# Power.net
KiCad netlist of a schematic drawn in Altium Designer
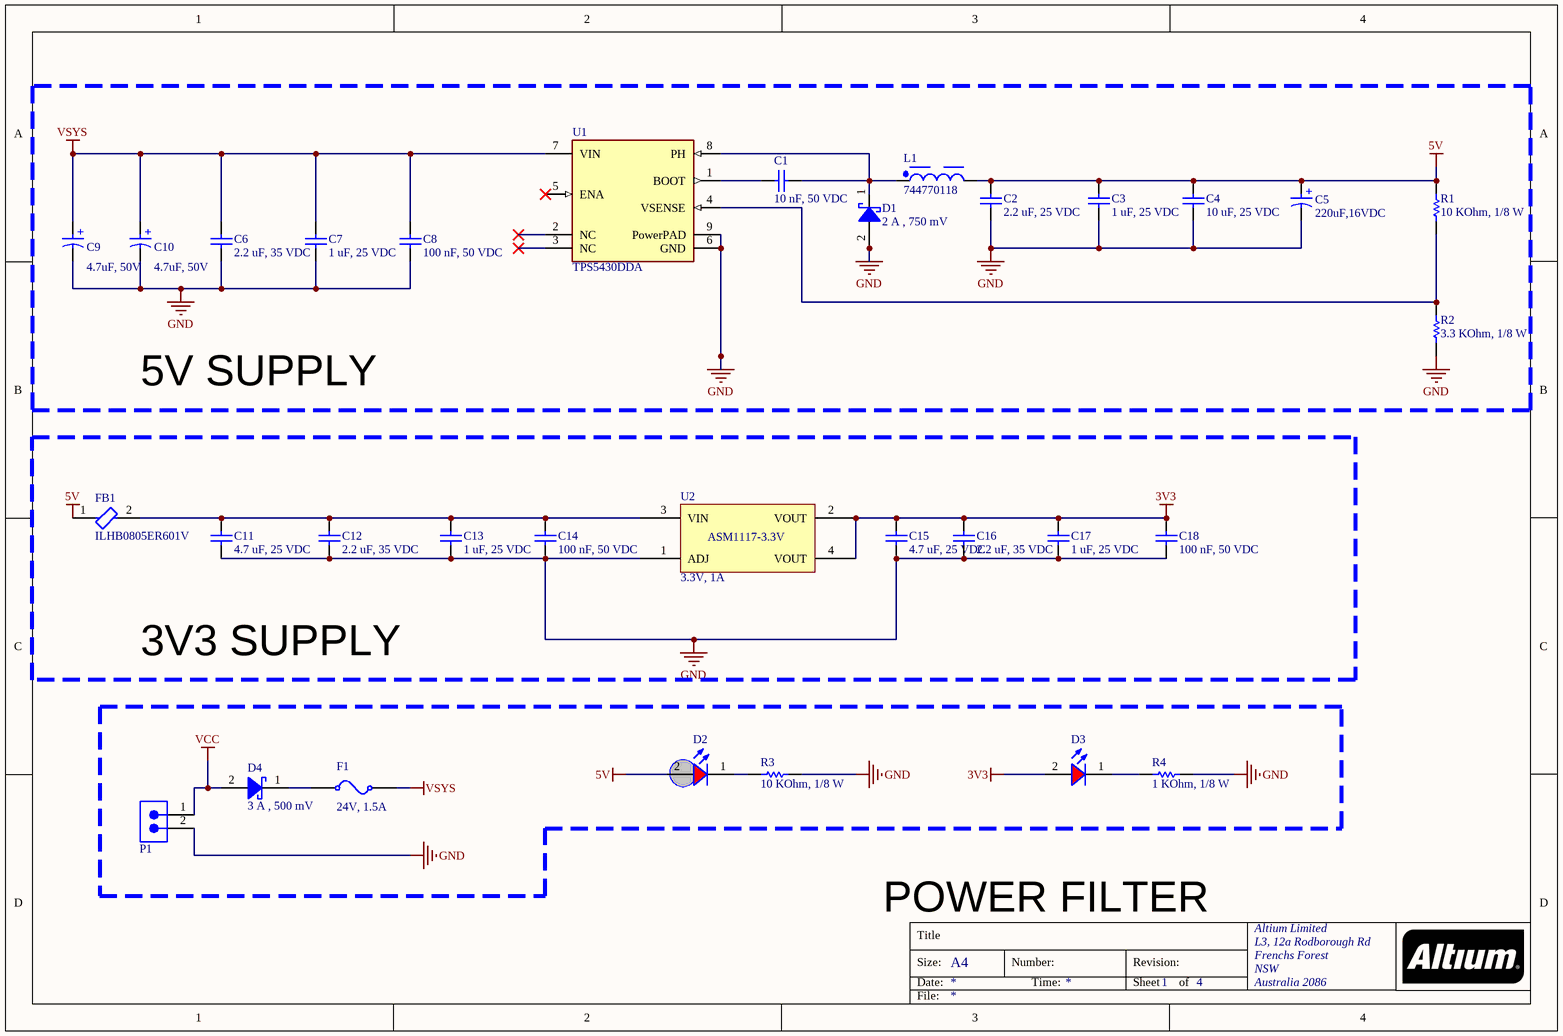
[diagram p0: Power.SchDoc]

(export (version "E")
  (design (tool "Eeschema 10.0.6"))
  (components
    (comp (ref "C1")
      (value "10 nF, 50 VDC")
      (footprint "CAP_0805")
      (description "CAP, size 0805, 10 nF, 50 VDC")
      (fields (field (name "TOLERANCE") "+/-5%"))
      (libsource (lib "Altium_Ceramic_Cap") (part "0108051031050"))
    )
    (comp (ref "C2")
      (value "2.2 uF, 25 VDC")
      (footprint "CAP_0805")
      (description "CAP, size 0805, 2.2 uF, 25 VDC")
      (fields (field (name "TOLERANCE") "+/-10%"))
      (libsource (lib "Altium_Ceramic_Cap") (part "0108052251025"))
    )
    (comp (ref "C3")
      (value "1 uF, 25 VDC")
      (footprint "CAP_0805")
      (description "CAP, size 0805, 1 uF, 25 VDC")
      (fields (field (name "TOLERANCE") "+/-10%"))
      (libsource (lib "Altium_Ceramic_Cap") (part "0108051051025"))
    )
    (comp (ref "C4")
      (value "10 uF, 25 VDC")
      (footprint "CAP_0805")
      (description "CAP, size 0805, 10 uF, 25 VDC")
      (fields (field (name "TOLERANCE") "+/-10%"))
      (libsource (lib "Altium_Ceramic_Cap") (part "0108051061025"))
    )
    (comp (ref "C5")
      (value "220uF,16VDC")
      (footprint "WCAP-ASLI_D6.3H7.7")
      (description "V-Chip, D6.3 x H7.7mm, 220uF, 16V")
      (fields (field (name "MANUFACTURER") "Wurth Elektronik"))
      (libsource (lib "Altium_Alutinum_Cap") (part "865080345012"))
    )
    (comp (ref "C6")
      (value "2.2 uF, 35 VDC")
      (footprint "CAP_0805")
      (description "CAP, size 0805, 2.2 uF, 35 VDC")
      (fields (field (name "TOLERANCE") "+/-10%"))
      (libsource (lib "Altium_Ceramic_Cap") (part "0108052251035"))
    )
    (comp (ref "C7")
      (value "1 uF, 25 VDC")
      (footprint "CAP_0805")
      (description "CAP, size 0805, 1 uF, 25 VDC")
      (fields (field (name "TOLERANCE") "+/-10%"))
      (libsource (lib "Altium_Ceramic_Cap") (part "0108051051025"))
    )
    (comp (ref "C8")
      (value "100 nF, 50 VDC")
      (footprint "CAP_0805")
      (description "CAP, size 0805, 100 nF, 50 VDC")
      (fields (field (name "TOLERANCE") "+/-10%"))
      (libsource (lib "Altium_Ceramic_Cap") (part "0108051041050"))
    )
    (comp (ref "C9")
      (value "4.7uF, 50V")
      (footprint "WCAP-ASLI_D4H5.5")
      (description "V-Chip, D4 x H5.5mm, 4.7uF, 50V")
      (fields (field (name "MANUFACTURER") "Wurth Elektronik"))
      (libsource (lib "Altium_Alutinum_Cap") (part "865080640004"))
    )
    (comp (ref "C10")
      (value "4.7uF, 50V")
      (footprint "WCAP-ASLI_D4H5.5")
      (description "V-Chip, D4 x H5.5mm, 4.7uF, 50V")
      (fields (field (name "MANUFACTURER") "Wurth Elektronik"))
      (libsource (lib "Altium_Alutinum_Cap") (part "865080640004"))
    )
    (comp (ref "C11")
      (value "4.7 uF, 25 VDC")
      (footprint "CAP_0805")
      (description "CAP, size 0805, 4.7 uF, 25 VDC")
      (fields (field (name "TOLERANCE") "+/-10%"))
      (libsource (lib "Altium_Ceramic_Cap") (part "0108054751025"))
    )
    (comp (ref "C12")
      (value "2.2 uF, 35 VDC")
      (footprint "CAP_0805")
      (description "CAP, size 0805, 2.2 uF, 35 VDC")
      (fields (field (name "TOLERANCE") "+/-10%"))
      (libsource (lib "Altium_Ceramic_Cap") (part "0108052251035"))
    )
    (comp (ref "C13")
      (value "1 uF, 25 VDC")
      (footprint "CAP_0805")
      (description "CAP, size 0805, 1 uF, 25 VDC")
      (fields (field (name "TOLERANCE") "+/-10%"))
      (libsource (lib "Altium_Ceramic_Cap") (part "0108051051025"))
    )
    (comp (ref "C14")
      (value "100 nF, 50 VDC")
      (footprint "CAP_0805")
      (description "CAP, size 0805, 100 nF, 50 VDC")
      (fields (field (name "TOLERANCE") "+/-10%"))
      (libsource (lib "Altium_Ceramic_Cap") (part "0108051041050"))
    )
    (comp (ref "C15")
      (value "4.7 uF, 25 VDC")
      (footprint "CAP_0805")
      (description "CAP, size 0805, 4.7 uF, 25 VDC")
      (fields (field (name "TOLERANCE") "+/-10%"))
      (libsource (lib "Altium_Ceramic_Cap") (part "0108054751025"))
    )
    (comp (ref "C16")
      (value "2.2 uF, 35 VDC")
      (footprint "CAP_0805")
      (description "CAP, size 0805, 2.2 uF, 35 VDC")
      (fields (field (name "TOLERANCE") "+/-10%"))
      (libsource (lib "Altium_Ceramic_Cap") (part "0108052251035"))
    )
    (comp (ref "C17")
      (value "1 uF, 25 VDC")
      (footprint "CAP_0805")
      (description "CAP, size 0805, 1 uF, 25 VDC")
      (fields (field (name "TOLERANCE") "+/-10%"))
      (libsource (lib "Altium_Ceramic_Cap") (part "0108051051025"))
    )
    (comp (ref "C18")
      (value "100 nF, 50 VDC")
      (footprint "CAP_0805")
      (description "CAP, size 0805, 100 nF, 50 VDC")
      (fields (field (name "TOLERANCE") "+/-10%"))
      (libsource (lib "Altium_Ceramic_Cap") (part "0108051041050"))
    )
    (comp (ref "D1")
      (value "2 A , 750 mV")
      (footprint "SMA (DO-214AC)")
      (description "Schottky Diodes & Rectifiers 2.0 Amp 60 Volt 40 Amp IFSM")
      (fields
        (field (name "MANUFACTURER") "Vishay Semiconductors")
        (field (name "MANUFACTURER PART NUMBER") "SS26S-E3/5AT")
      )
      (libsource (lib "Altium_Diode") (part "SS26"))
    )
    (comp (ref "D2")
      (value "Red, 2V")
      (footprint "WL-SMCW_0805")
      (description "WL-SMCW SMT Mono-color Chip LED Blur, size 0805, Red, 2V, 140deg")
      (libsource (lib "Altium_LED") (part "160805RedBlur"))
    )
    (comp (ref "D3")
      (value "Red, 2V")
      (footprint "WL-SMCW_0805")
      (description "WL-SMCW SMT Mono-color Chip LED Blur, size 0805, Red, 2V, 140deg")
      (libsource (lib "Altium_LED") (part "160805RedBlur"))
    )
    (comp (ref "D4")
      (value "3 A , 500 mV")
      (footprint "SMC (DO-214AB)")
      (description "Schottky Diodes & Rectifiers 3.0 Amp 40 Volt")
      (fields
        (field (name "MANUFACTURER") "Vishay Semiconductors")
        (field (name "MANUFACTURER PART NUMBER") "SS34-E3/57T")
      )
      (libsource (lib "Altium_Diode") (part "SS34"))
    )
    (comp (ref "F1")
      (value "24V, 1.5A")
      (footprint "Fuse_SMD_1812")
      (description "Resettable Fuse, Size 1812, 24V, 1.5A")
      (fields (field (name "MANUFACTURER") "Littelfuse"))
      (libsource (lib "Altium_Fuse") (part "061812150024"))
    )
    (comp (ref "FB1")
      (value "ILHB0805ER601V")
      (footprint "FP-ILHB-0805-IPC_C")
      (description "FERRITE BEAD 600 OHM 0805 1LN")
      (fields
        (field (name "TOLERANCE") "25%")
        (field (name "OCTOPART") "https://octopart.com/ilhb0805er601v-vishay-39650184")
      )
      (libsource (lib "Altium Content Vault") (part "5f30dd21d616792df468990f7003faa"))
    )
    (comp (ref "L1")
      (value "744770118")
      (footprint "WE-PD_1280")
      (libsource (lib "Altium Content Vault") (part "Inductor - 2"))
    )
    (comp (ref "P1")
      (value "20A, 300V")
      (footprint "Terminal-Block 2 pin")
      (fields
        (field (name "MANUFACTURER PART NUMBER") "691312510002")
        (field (name "MANUFACTURER") "Wurth Elektronik")
      )
      (libsource (lib "Altium_Terminal_Block") (part "691312510002"))
    )
    (comp (ref "R1")
      (value "10 KOhm, 1/8 W")
      (footprint "RESISTOR_0805")
      (description "RES, size 0805, 10 KOhm, 1/8 W")
      (libsource (lib "Altium_Resistor") (part "0008051035"))
    )
    (comp (ref "R2")
      (value "3.3 KOhm, 1/8 W")
      (footprint "RESISTOR_0805")
      (description "RES, size 0805, 3.3 KOhm, 1/8 W")
      (libsource (lib "Altium_Resistor") (part "0008053325"))
    )
    (comp (ref "R3")
      (value "10 KOhm, 1/8 W")
      (footprint "RESISTOR_0805")
      (description "RES, size 0805, 10 KOhm, 1/8 W")
      (libsource (lib "Altium_Resistor") (part "0008051031"))
    )
    (comp (ref "R4")
      (value "1 KOhm, 1/8 W")
      (footprint "RESISTOR_0805")
      (description "RES, size 0805, 1 KOhm, 1/8 W")
      (libsource (lib "Altium_Resistor") (part "0008051025"))
    )
    (comp (ref "U1")
      (value "TPS5430DDA")
      (footprint "FP-DDA0008J-MFG")
      (description "IC REG BUCK ADJUSTABLE 3A 8SOPWR")
      (fields
        (field (name "MANUFACTURER") "Texas Instruments")
        (field (name "OCTOPART") "https://octopart.com/tps5430dda-texas+instruments-589977")
      )
      (libsource (lib "Altium Content Vault") (part "98da629940cea6febc5630bb55159f3"))
    )
    (comp (ref "U2")
      (value "3.3V, 1A")
      (footprint "AMS1117-3.3V SOT223")
      (description "AMS1117-3.3V, OUT 3.3V 1A.")
      (fields (field (name "MANUFACTURER") "AMS"))
      (libsource (lib "Altium_Power_Supply_IC") (part "AMS1117-3.3V"))
    )
  )
  (nets
    (net (code "1") (name "3V3") (class "Default")
      (node (ref "C15") (pin "2") (pinfunction "2_2") (pintype "passive"))
      (node (ref "C16") (pin "2") (pinfunction "2_2") (pintype "passive"))
      (node (ref "C17") (pin "2") (pinfunction "2_2") (pintype "passive"))
      (node (ref "C18") (pin "2") (pinfunction "2_2") (pintype "passive"))
      (node (ref "D3") (pin "2") (pinfunction "A_2") (pintype "passive"))
      (node (ref "U2") (pin "2") (pinfunction "VOUT_2") (pintype "passive"))
      (node (ref "U2") (pin "4") (pinfunction "VOUT_4") (pintype "power_in"))
    )
    (net (code "2") (name "5V") (class "Default")
      (node (ref "C2") (pin "2") (pinfunction "2_2") (pintype "passive"))
      (node (ref "C3") (pin "2") (pinfunction "2_2") (pintype "passive"))
      (node (ref "C4") (pin "2") (pinfunction "2_2") (pintype "passive"))
      (node (ref "C5") (pin "1") (pinfunction "P_1") (pintype "passive"))
      (node (ref "D2") (pin "2") (pinfunction "A_2") (pintype "passive"))
      (node (ref "FB1") (pin "1") (pinfunction "1_1") (pintype "passive"))
      (node (ref "L1") (pin "2") (pinfunction "2_2") (pintype "passive"))
      (node (ref "R1") (pin "2") (pinfunction "2_2") (pintype "passive"))
    )
    (net (code "3") (name "GND") (class "Default")
      (node (ref "C10") (pin "2") (pinfunction "N_2") (pintype "passive"))
      (node (ref "C11") (pin "1") (pinfunction "1_1") (pintype "passive"))
      (node (ref "C12") (pin "1") (pinfunction "1_1") (pintype "passive"))
      (node (ref "C13") (pin "1") (pinfunction "1_1") (pintype "passive"))
      (node (ref "C14") (pin "1") (pinfunction "1_1") (pintype "passive"))
      (node (ref "C15") (pin "1") (pinfunction "1_1") (pintype "passive"))
      (node (ref "C16") (pin "1") (pinfunction "1_1") (pintype "passive"))
      (node (ref "C17") (pin "1") (pinfunction "1_1") (pintype "passive"))
      (node (ref "C18") (pin "1") (pinfunction "1_1") (pintype "passive"))
      (node (ref "C2") (pin "1") (pinfunction "1_1") (pintype "passive"))
      (node (ref "C3") (pin "1") (pinfunction "1_1") (pintype "passive"))
      (node (ref "C4") (pin "1") (pinfunction "1_1") (pintype "passive"))
      (node (ref "C5") (pin "2") (pinfunction "N_2") (pintype "passive"))
      (node (ref "C6") (pin "1") (pinfunction "1_1") (pintype "passive"))
      (node (ref "C7") (pin "1") (pinfunction "1_1") (pintype "passive"))
      (node (ref "C8") (pin "1") (pinfunction "1_1") (pintype "passive"))
      (node (ref "C9") (pin "2") (pinfunction "N_2") (pintype "passive"))
      (node (ref "D1") (pin "2") (pinfunction "A_2") (pintype "passive"))
      (node (ref "P1") (pin "2") (pinfunction "2_2") (pintype "passive"))
      (node (ref "R2") (pin "1") (pinfunction "1_1") (pintype "passive"))
      (node (ref "R3") (pin "1") (pinfunction "1_1") (pintype "passive"))
      (node (ref "R4") (pin "1") (pinfunction "1_1") (pintype "passive"))
      (node (ref "U1") (pin "6") (pinfunction "GND_6") (pintype "power_in"))
      (node (ref "U1") (pin "9") (pinfunction "PowerPAD_9") (pintype "power_in"))
      (node (ref "U2") (pin "1") (pinfunction "ADJ_1") (pintype "power_in"))
    )
    (net (code "4") (name "Net-(D1-K)") (class "Default")
      (node (ref "C1") (pin "1") (pinfunction "1_1") (pintype "passive"))
      (node (ref "D1") (pin "1") (pinfunction "K_1") (pintype "passive"))
      (node (ref "L1") (pin "1") (pinfunction "1_1") (pintype "passive"))
      (node (ref "U1") (pin "8") (pinfunction "PH_8") (pintype "input"))
    )
    (net (code "5") (name "Net-(D2-K)") (class "Default")
      (node (ref "D2") (pin "1") (pinfunction "K_1") (pintype "passive"))
      (node (ref "R3") (pin "2") (pinfunction "2_2") (pintype "passive"))
    )
    (net (code "6") (name "Net-(D3-K)") (class "Default")
      (node (ref "D3") (pin "1") (pinfunction "K_1") (pintype "passive"))
      (node (ref "R4") (pin "2") (pinfunction "2_2") (pintype "passive"))
    )
    (net (code "7") (name "Net-(D4-K)") (class "Default")
      (node (ref "D4") (pin "1") (pinfunction "K_1") (pintype "passive"))
      (node (ref "F1") (pin "0") (pinfunction "0_0") (pintype "passive"))
    )
    (net (code "8") (name "Net-(U1-BOOT)") (class "Default")
      (node (ref "C1") (pin "2") (pinfunction "2_2") (pintype "passive"))
      (node (ref "U1") (pin "1") (pinfunction "BOOT_1") (pintype "output"))
    )
    (net (code "9") (name "Net-(U1-VSENSE)") (class "Default")
      (node (ref "R1") (pin "1") (pinfunction "1_1") (pintype "passive"))
      (node (ref "R2") (pin "2") (pinfunction "2_2") (pintype "passive"))
      (node (ref "U1") (pin "4") (pinfunction "VSENSE_4") (pintype "input"))
    )
    (net (code "10") (name "Net-(U2-VIN)") (class "Default")
      (node (ref "C11") (pin "2") (pinfunction "2_2") (pintype "passive"))
      (node (ref "C12") (pin "2") (pinfunction "2_2") (pintype "passive"))
      (node (ref "C13") (pin "2") (pinfunction "2_2") (pintype "passive"))
      (node (ref "C14") (pin "2") (pinfunction "2_2") (pintype "passive"))
      (node (ref "FB1") (pin "2") (pinfunction "2_2") (pintype "passive"))
      (node (ref "U2") (pin "3") (pinfunction "VIN_3") (pintype "passive"))
    )
    (net (code "11") (name "VCC") (class "Default")
      (node (ref "D4") (pin "2") (pinfunction "A_2") (pintype "passive"))
      (node (ref "P1") (pin "1") (pinfunction "1_1") (pintype "passive"))
    )
    (net (code "12") (name "VSYS") (class "Default")
      (node (ref "C10") (pin "1") (pinfunction "P_1") (pintype "passive"))
      (node (ref "C6") (pin "2") (pinfunction "2_2") (pintype "passive"))
      (node (ref "C7") (pin "2") (pinfunction "2_2") (pintype "passive"))
      (node (ref "C8") (pin "2") (pinfunction "2_2") (pintype "passive"))
      (node (ref "C9") (pin "1") (pinfunction "P_1") (pintype "passive"))
      (node (ref "F1") (pin "1") (pinfunction "1_1") (pintype "passive"))
      (node (ref "U1") (pin "7") (pinfunction "VIN_7") (pintype "power_in"))
    )
    (net (code "13") (name "unconnected-(U1-ENA-Pad5)") (class "Default")
      (node (ref "U1") (pin "5") (pinfunction "ENA_5") (pintype "input+no_connect"))
    )
    (net (code "14") (name "unconnected-(U1-NC-Pad2)") (class "Default")
      (node (ref "U1") (pin "2") (pinfunction "NC_2") (pintype "passive+no_connect"))
    )
    (net (code "15") (name "unconnected-(U1-NC-Pad3)") (class "Default")
      (node (ref "U1") (pin "3") (pinfunction "NC_3") (pintype "passive+no_connect"))
    )
  )
)
